# MCU.net
KiCad netlist of a schematic drawn in Altium Designer
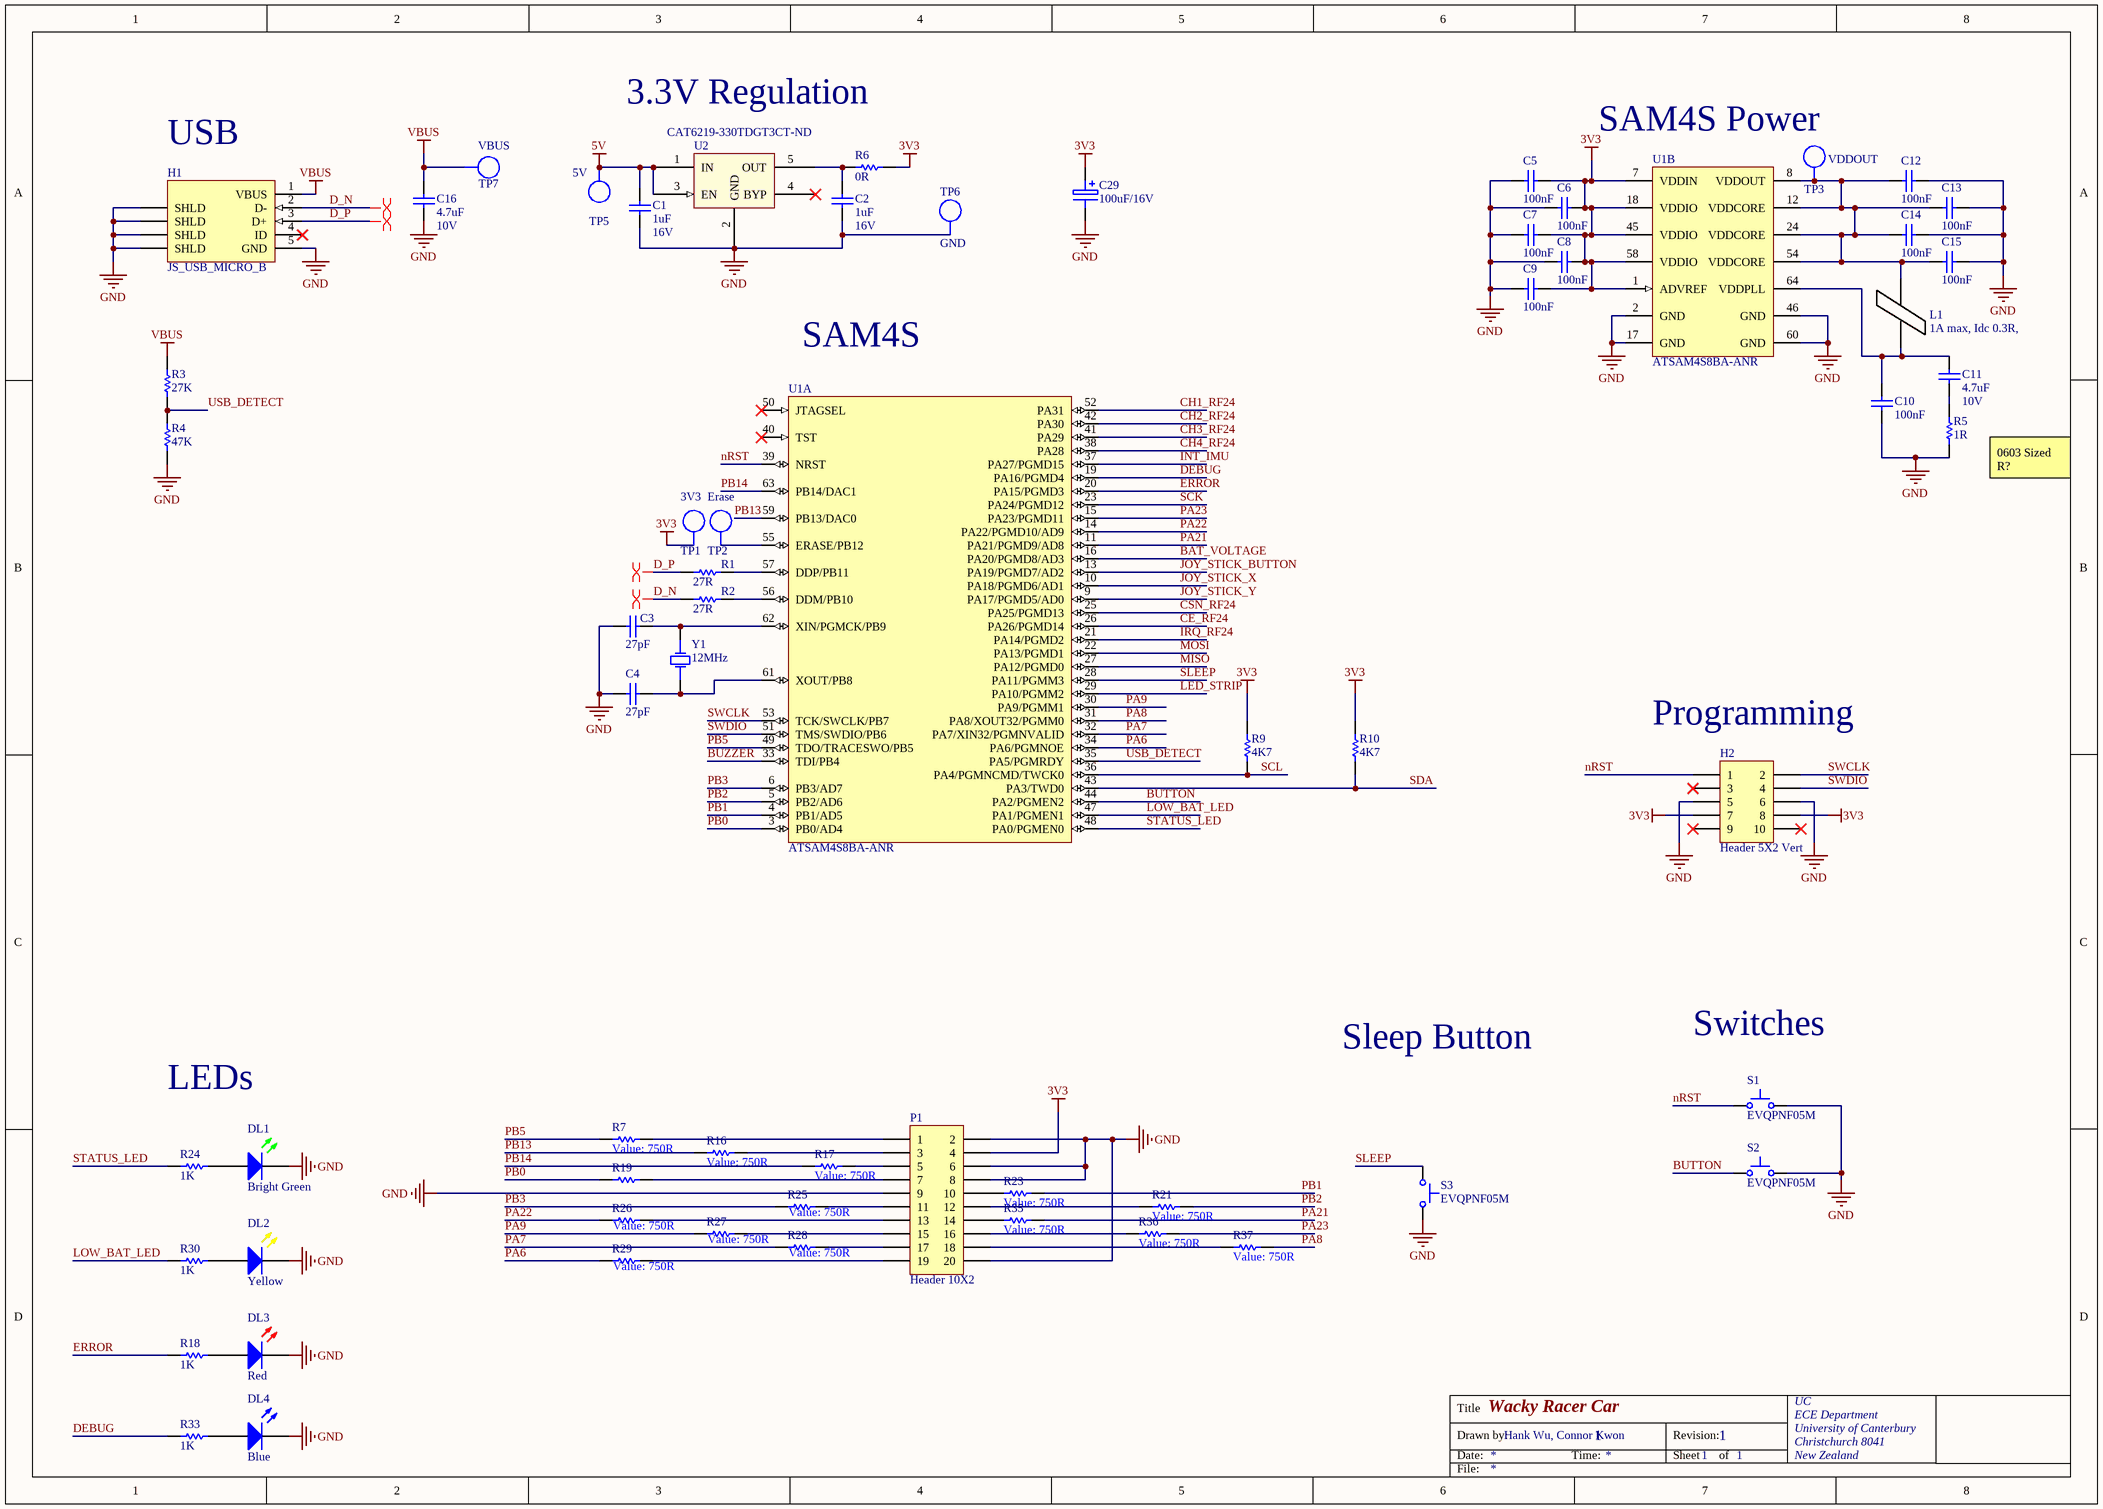
[diagram p0: MCU.SchDoc]

(export (version "E")
  (design (tool "Eeschema 10.0.6"))
  (components
    (comp (ref "C1")
      (value "1uF")
      (footprint "CAPC1608L")
      (description "CAP CER 1uF Y5V -20% +80% 16V 0603")
      (fields (field (name "MAX VOLTAGE") "16V"))
      (libsource (lib "ECE AD19Components_19V1") (part "CC_1uF_0603"))
    )
    (comp (ref "C2")
      (value "1uF")
      (footprint "CAPC1608L")
      (description "CAP CER 1uF Y5V -20% +80% 16V 0603")
      (fields (field (name "MAX VOLTAGE") "16V"))
      (libsource (lib "ECE AD19Components_19V1") (part "CC_1uF_0603"))
    )
    (comp (ref "C3")
      (value "27pF")
      (footprint "CAPC1608L")
      (description "CAP CER 27pF NPO/COG +-5% 50V 0603")
      (libsource (lib "ECE AD19Components_19V1") (part "CC_27pF_0603"))
    )
    (comp (ref "C4")
      (value "27pF")
      (footprint "CAPC1608L")
      (description "CAP CER 27pF NPO/COG +-5% 50V 0603")
      (libsource (lib "ECE AD19Components_19V1") (part "CC_27pF_0603"))
    )
    (comp (ref "C5")
      (value "100nF")
      (footprint "CAPC1608L")
      (description "CAP CER 100nF X7R +-10% 50V 0603")
      (libsource (lib "ECE AD19Components_19V1") (part "CC_100nF_0603"))
    )
    (comp (ref "C6")
      (value "100nF")
      (footprint "CAPC1608L")
      (description "CAP CER 100nF X7R +-10% 50V 0603")
      (libsource (lib "ECE AD19Components_19V1") (part "CC_100nF_0603"))
    )
    (comp (ref "C7")
      (value "100nF")
      (footprint "CAPC1608L")
      (description "CAP CER 100nF X7R +-10% 50V 0603")
      (libsource (lib "ECE AD19Components_19V1") (part "CC_100nF_0603"))
    )
    (comp (ref "C8")
      (value "100nF")
      (footprint "CAPC1608L")
      (description "CAP CER 100nF X7R +-10% 50V 0603")
      (libsource (lib "ECE AD19Components_19V1") (part "CC_100nF_0603"))
    )
    (comp (ref "C9")
      (value "100nF")
      (footprint "CAPC1608L")
      (description "CAP CER 100nF X7R +-10% 50V 0603")
      (libsource (lib "ECE AD19Components_19V1") (part "CC_100nF_0603"))
    )
    (comp (ref "C10")
      (value "100nF")
      (footprint "CAPC1608L")
      (description "CAP CER 100nF X7R +-10% 50V 0603")
      (libsource (lib "ECE AD19Components_19V1") (part "CC_100nF_0603"))
    )
    (comp (ref "C11")
      (value "4.7uF")
      (footprint "CAPC1608N")
      (description "CAP CER 4.7uF X5R +-20%  10V 0603")
      (fields (field (name "MAX VOLTAGE") "10V"))
      (libsource (lib "ECE AD19Components_19V1") (part "CC_4.7uF_0603"))
    )
    (comp (ref "C12")
      (value "100nF")
      (footprint "CAPC1608L")
      (description "CAP CER 100nF X7R +-10% 50V 0603")
      (libsource (lib "ECE AD19Components_19V1") (part "CC_100nF_0603"))
    )
    (comp (ref "C13")
      (value "100nF")
      (footprint "CAPC1608L")
      (description "CAP CER 100nF X7R +-10% 50V 0603")
      (libsource (lib "ECE AD19Components_19V1") (part "CC_100nF_0603"))
    )
    (comp (ref "C14")
      (value "100nF")
      (footprint "CAPC1608L")
      (description "CAP CER 100nF X7R +-10% 50V 0603")
      (libsource (lib "ECE AD19Components_19V1") (part "CC_100nF_0603"))
    )
    (comp (ref "C15")
      (value "100nF")
      (footprint "CAPC1608L")
      (description "CAP CER 100nF X7R +-10% 50V 0603")
      (libsource (lib "ECE AD19Components_19V1") (part "CC_100nF_0603"))
    )
    (comp (ref "C16")
      (value "4.7uF")
      (footprint "CAPC1608N")
      (description "CAP CER 4.7uF X5R +-20%  10V 0603")
      (fields (field (name "MAX VOLTAGE") "10V"))
      (libsource (lib "ECE AD19Components_19V1") (part "CC_4.7uF_0603"))
    )
    (comp (ref "C29")
      (value "100uF/16V")
      (footprint "NICH-1")
      (description "CAP ALUM 100uF 16V SMD")
      (fields (field (name "MANUFACTURER") "Nichcon"))
      (libsource (lib "ECE AD19Components_19V1") (part "CA_100uF_16V"))
    )
    (comp (ref "DL1")
      (value "Bright Green")
      (footprint "WL-SMCW0603")
      (description "LED Bright Green 40mcd 0603 SMD")
      (fields
        (field (name "MANUFACTURER") "WURTH ELEKTRONIK")
        (field (name "MANUFACTURER PART NUMBER") "150060VS75000")
        (field (name "LED COLOUR") "Bright Green")
      )
      (libsource (lib "ECE AD19Components_19V1") (part "DL_150060VS75000"))
    )
    (comp (ref "DL2")
      (value "Yellow")
      (footprint "WL-SMCW0603")
      (description "LED Yellow 120mcd 0603 SMD")
      (fields
        (field (name "MANUFACTURER") "WURTH ELEKTRONIK")
        (field (name "MANUFACTURER PART NUMBER") "150060YS75000")
        (field (name "LED COLOUR") "Yellow")
      )
      (libsource (lib "ECE AD19Components_19V1") (part "DL_150060YS75000"))
    )
    (comp (ref "DL3")
      (value "Red")
      (footprint "WL-SMCW0603")
      (description "LED Red 250mcd 0603 SMD")
      (fields
        (field (name "MANUFACTURER") "WURTH ELEKTRONIK")
        (field (name "MANUFACTURER PART NUMBER") "150060RS75000")
        (field (name "LED COLOUR") "Red")
      )
      (libsource (lib "ECE AD19Components_19V1") (part "DL_150060RS75000"))
    )
    (comp (ref "DL4")
      (value "Blue")
      (footprint "WL-SMCW0603")
      (description "LED Blue 270mcd 0603 SMD")
      (fields
        (field (name "MANUFACTURER") "WURTH ELEKTRONIK")
        (field (name "MANUFACTURER PART NUMBER") "150060BS75000")
        (field (name "LED COLOUR") "Blue")
      )
      (libsource (lib "ECE AD19Components_19V1") (part "DL_150060BS75000"))
    )
    (comp (ref "H1")
      (value "JS_USB_MICRO_B")
      (footprint "FCI_USB_10118194-0001LF")
      (description "CONN USB MICRO B RECPT SMT R/A")
      (fields (field (name "MANUFACTURER") "FCI") (field (name "MANUFACTURER PART NUMBER") "10118194-0001LF"))
      (libsource (lib "ECE AD19Components_19V1") (part "JS_USB_MICRO_B_SMT"))
    )
    (comp (ref "H2")
      (value "Header 5X2 Vert")
      (footprint "IDC2.54-V10D")
      (description "IDC Header, 2,54mm, 10-Pin, Vert")
      (libsource (lib "ECE AD19Components_19V1") (part "JA_HDR_IDC_5X2_VERT"))
    )
    (comp (ref "L1")
      (value "1A max, Idc 0.3R,")
      (footprint "INDC3216L")
      (description "Ferrite Bead, Rdc 0.3R, Z100MHZ 600R, Imax 1A, SMD 1206")
      (fields
        (field (name "MANUFACTURER") "FAIR-RITE")
        (field (name "MANUFACTURER PART NUMBER") "2512066017Y1")
      )
      (libsource (lib "ECE AD19Components_19V1") (part "IN_Ferrite-Bead"))
    )
    (comp (ref "P1")
      (value "Header 10X2")
      (footprint "HDR2X10")
      (description "Header, 10-Pin, Dual row")
      (fields (field (name "PUBLISHER") "Altium Limited"))
      (libsource (lib "Miscellaneous Connectors") (part "Header 10X2"))
    )
    (comp (ref "R1")
      (value "27R")
      (footprint "RESC1608L")
      (description "RES 27 OHM 1/10W 5% 0603 SMD")
      (libsource (lib "ECE AD19Components_19V1") (part "RS_27R"))
    )
    (comp (ref "R2")
      (value "27R")
      (footprint "RESC1608L")
      (description "RES 27 OHM 1/10W 5% 0603 SMD")
      (libsource (lib "ECE AD19Components_19V1") (part "RS_27R"))
    )
    (comp (ref "R3")
      (value "27K")
      (footprint "RESC1608L")
      (description "RES 27K OHM 1/10W 5% 0603 SMD")
      (libsource (lib "ECE AD19Components_19V1") (part "RS_27K"))
    )
    (comp (ref "R4")
      (value "47K")
      (footprint "RESC1608L")
      (description "RES 27K OHM 1/10W 5% 0603 SMD")
      (libsource (lib "ECE AD19Components_19V1") (part "RS_27K"))
    )
    (comp (ref "R5")
      (value "1R")
      (footprint "RESC3216L")
      (description "RES 1R OHM 1/4W 5% 1206 SMD")
      (libsource (lib "ECE AD19Components_19V1") (part "RT_1R"))
    )
    (comp (ref "R6")
      (value "0R")
      (footprint "RESC1608L")
      (description "RES 0.0 OHM 1/10W 5% 0603 SMD")
      (libsource (lib "ECE AD19Components_19V1") (part "RS_0R0"))
    )
    (comp (ref "R7")
      (value "750R")
      (footprint "RESC1608L")
      (description "RES 750 OHM 1/10W 5% 0603 SMD")
      (libsource (lib "ECE AD19Components_19V1") (part "RS_750R"))
    )
    (comp (ref "R9")
      (value "4K7")
      (footprint "RESC1608L")
      (description "RES 4.7K OHM 1/10W 5% 0603 SMD")
      (libsource (lib "ECE AD19Components_19V1") (part "RS_4K7"))
    )
    (comp (ref "R10")
      (value "4K7")
      (footprint "RESC1608L")
      (description "RES 4.7K OHM 1/10W 5% 0603 SMD")
      (libsource (lib "ECE AD19Components_19V1") (part "RS_4K7"))
    )
    (comp (ref "R16")
      (value "750R")
      (footprint "RESC1608L")
      (description "RES 750 OHM 1/10W 5% 0603 SMD")
      (libsource (lib "ECE AD19Components_19V1") (part "RS_750R"))
    )
    (comp (ref "R17")
      (value "750R")
      (footprint "RESC1608L")
      (description "RES 750 OHM 1/10W 5% 0603 SMD")
      (libsource (lib "ECE AD19Components_19V1") (part "RS_750R"))
    )
    (comp (ref "R18")
      (value "1K")
      (footprint "RESC1608L")
      (description "RES 1.0K OHM 1/10W 5% 0603 SMD")
      (libsource (lib "ECE AD19Components_19V1") (part "RS_1K"))
    )
    (comp (ref "R19")
      (value "~")
      (footprint "RESC1608L")
      (description "RES 750 OHM 1/10W 5% 0603 SMD")
      (libsource (lib "ECE AD19Components_19V1") (part "RS_750R"))
    )
    (comp (ref "R21")
      (value "750R")
      (footprint "RESC1608L")
      (description "RES 750 OHM 1/10W 5% 0603 SMD")
      (libsource (lib "ECE AD19Components_19V1") (part "RS_750R"))
    )
    (comp (ref "R23")
      (value "750R")
      (footprint "RESC1608L")
      (description "RES 750 OHM 1/10W 5% 0603 SMD")
      (libsource (lib "ECE AD19Components_19V1") (part "RS_750R"))
    )
    (comp (ref "R24")
      (value "1K")
      (footprint "RESC1608L")
      (description "RES 1.0K OHM 1/10W 5% 0603 SMD")
      (libsource (lib "ECE AD19Components_19V1") (part "RS_1K"))
    )
    (comp (ref "R25")
      (value "750R")
      (footprint "RESC1608L")
      (description "RES 750 OHM 1/10W 5% 0603 SMD")
      (libsource (lib "ECE AD19Components_19V1") (part "RS_750R"))
    )
    (comp (ref "R26")
      (value "750R")
      (footprint "RESC1608L")
      (description "RES 750 OHM 1/10W 5% 0603 SMD")
      (libsource (lib "ECE AD19Components_19V1") (part "RS_750R"))
    )
    (comp (ref "R27")
      (value "750R")
      (footprint "RESC1608L")
      (description "RES 750 OHM 1/10W 5% 0603 SMD")
      (libsource (lib "ECE AD19Components_19V1") (part "RS_750R"))
    )
    (comp (ref "R28")
      (value "750R")
      (footprint "RESC1608L")
      (description "RES 750 OHM 1/10W 5% 0603 SMD")
      (libsource (lib "ECE AD19Components_19V1") (part "RS_750R"))
    )
    (comp (ref "R29")
      (value "750R")
      (footprint "RESC1608L")
      (description "RES 750 OHM 1/10W 5% 0603 SMD")
      (libsource (lib "ECE AD19Components_19V1") (part "RS_750R"))
    )
    (comp (ref "R30")
      (value "1K")
      (footprint "RESC1608L")
      (description "RES 1.0K OHM 1/10W 5% 0603 SMD")
      (libsource (lib "ECE AD19Components_19V1") (part "RS_1K"))
    )
    (comp (ref "R33")
      (value "1K")
      (footprint "RESC1608L")
      (description "RES 1.0K OHM 1/10W 5% 0603 SMD")
      (libsource (lib "ECE AD19Components_19V1") (part "RS_1K"))
    )
    (comp (ref "R35")
      (value "750R")
      (footprint "RESC1608L")
      (description "RES 750 OHM 1/10W 5% 0603 SMD")
      (libsource (lib "ECE AD19Components_19V1") (part "RS_750R"))
    )
    (comp (ref "R36")
      (value "750R")
      (footprint "RESC1608L")
      (description "RES 750 OHM 1/10W 5% 0603 SMD")
      (libsource (lib "ECE AD19Components_19V1") (part "RS_750R"))
    )
    (comp (ref "R37")
      (value "750R")
      (footprint "RESC1608L")
      (description "RES 750 OHM 1/10W 5% 0603 SMD")
      (libsource (lib "ECE AD19Components_19V1") (part "RS_750R"))
    )
    (comp (ref "S1")
      (value "EVQPNF05M")
      (footprint "EVQPNF05M")
      (description "Panasonic 6 x 3.5mm SMD Light Touch Switch Type SMD")
      (fields (field (name "MANUFACTURER") "Panasonic"))
      (libsource (lib "ECE AD19Components_19V1") (part "WS_EVQPNF05M"))
    )
    (comp (ref "S2")
      (value "EVQPNF05M")
      (footprint "EVQPNF05M")
      (description "Panasonic 6 x 3.5mm SMD Light Touch Switch Type SMD")
      (fields (field (name "MANUFACTURER") "Panasonic"))
      (libsource (lib "ECE AD19Components_19V1") (part "WS_EVQPNF05M"))
    )
    (comp (ref "S3")
      (value "EVQPNF05M")
      (footprint "EVQPNF05M")
      (description "Panasonic 6 x 3.5mm SMD Light Touch Switch Type SMD")
      (fields (field (name "MANUFACTURER") "Panasonic"))
      (libsource (lib "ECE AD19Components_19V1") (part "WS_EVQPNF05M"))
    )
    (comp (ref "TP1")
      (value "3V3")
      (footprint "TP_1206")
      (description "Test-Point 3.3x1.6x2.1mm SMD")
      (fields
        (field (name "MANUFACTURER") "Harwin Inc")
        (field (name "MANUFACTURER PART NUMBER") "S1751-46R")
      )
      (libsource (lib "ECE AD19Components_19V1") (part "TP_1206"))
    )
    (comp (ref "TP2")
      (value "Erase")
      (footprint "TP_1206")
      (description "Test-Point 3.3x1.6x2.1mm SMD")
      (fields
        (field (name "MANUFACTURER") "Harwin Inc")
        (field (name "MANUFACTURER PART NUMBER") "S1751-46R")
      )
      (libsource (lib "ECE AD19Components_19V1") (part "TP_1206"))
    )
    (comp (ref "TP3")
      (value "VDDOUT")
      (footprint "TP_1206")
      (description "Test-Point 3.3x1.6x2.1mm SMD")
      (fields
        (field (name "MANUFACTURER") "Harwin Inc")
        (field (name "MANUFACTURER PART NUMBER") "S1751-46R")
      )
      (libsource (lib "ECE AD19Components_19V1") (part "TP_1206"))
    )
    (comp (ref "TP5")
      (value "5V")
      (footprint "TP_1206")
      (description "Test-Point 3.3x1.6x2.1mm SMD")
      (fields
        (field (name "MANUFACTURER") "Harwin Inc")
        (field (name "MANUFACTURER PART NUMBER") "S1751-46R")
      )
      (libsource (lib "ECE AD19Components_19V1") (part "TP_1206"))
    )
    (comp (ref "TP6")
      (value "GND")
      (footprint "TP_1206")
      (description "Test-Point 3.3x1.6x2.1mm SMD")
      (fields
        (field (name "MANUFACTURER") "Harwin Inc")
        (field (name "MANUFACTURER PART NUMBER") "S1751-46R")
      )
      (libsource (lib "ECE AD19Components_19V1") (part "TP_1206"))
    )
    (comp (ref "TP7")
      (value "VBUS")
      (footprint "TP_1206")
      (description "Test-Point 3.3x1.6x2.1mm SMD")
      (fields
        (field (name "MANUFACTURER") "Harwin Inc")
        (field (name "MANUFACTURER PART NUMBER") "S1751-46R")
      )
      (libsource (lib "ECE AD19Components_19V1") (part "TP_1206"))
    )
    (comp (ref "U1")
      (value "ATSAM4S8BA-ANR")
      (footprint "LQFP64_L")
      (description "IC MCU 32BIT 512KB FLASH 64LQFP")
      (fields (field (name "MANUFACTURER") "Atmel"))
      (libsource (lib "") (part "SE_ATSAM4S16BA-MU_1"))
    )
    (comp (ref "U2")
      (value "CAT6219-330TDGT3")
      (footprint "SOT95P280X145-5N")
      (description "IC REG LIN 3.3V 500MA TSOT23-5")
      (fields
        (field (name "BASE PART NUMBER") "CAT6219")
        (field (name "SUPPLIER PART NUMBER") "CAT6219-330TDGT3CT-ND")
      )
      (libsource (lib "ENCE461AD19_19V2") (part "SV_CAT6219-330TDGT3"))
    )
    (comp (ref "Y1")
      (value "12MHz")
      (footprint "6.0X3.5-4")
      (description "CRYSTAL 12MHZ 18PF 6X3.5mm SMD")
      (fields
        (field (name "MANUFACTURER") "CTS-Frequency Controls")
        (field (name "MANUFACTURER PART NUMBER") "406C35D12M00000")
        (field (name "FREQUENCY") "12MHz")
      )
      (libsource (lib "ECE AD19Components_19V1") (part "XT_CRYSTAL_12MHz_18pF"))
    )
  )
  (nets
    (net (code "1") (name "/BAT_VOLTAGE") (class "Default")
      (node (ref "U1") (pin "16") (pinfunction "PA20/PGMD8/AD3_16") (pintype "bidirectional"))
    )
    (net (code "2") (name "/BUTTON") (class "Default")
      (node (ref "S2") (pin "1") (pintype "passive"))
      (node (ref "U1") (pin "44") (pinfunction "PA2/PGMEN2_44") (pintype "bidirectional"))
    )
    (net (code "3") (name "/BUZZER") (class "Default")
      (node (ref "U1") (pin "33") (pinfunction "TDI/PB4_33") (pintype "bidirectional"))
    )
    (net (code "4") (name "/CE_RF24") (class "Default")
      (node (ref "U1") (pin "26") (pinfunction "PA26/PGMD14_26") (pintype "bidirectional"))
    )
    (net (code "5") (name "/CH1_RF24") (class "Default")
      (node (ref "U1") (pin "52") (pinfunction "PA31_52") (pintype "bidirectional"))
    )
    (net (code "6") (name "/CH2_RF24") (class "Default")
      (node (ref "U1") (pin "42") (pinfunction "PA30_42") (pintype "bidirectional"))
    )
    (net (code "7") (name "/CH3_RF24") (class "Default")
      (node (ref "U1") (pin "41") (pinfunction "PA29_41") (pintype "bidirectional"))
    )
    (net (code "8") (name "/CH4_RF24") (class "Default")
      (node (ref "U1") (pin "38") (pinfunction "PA28_38") (pintype "bidirectional"))
    )
    (net (code "9") (name "/CSN_RF24") (class "Default")
      (node (ref "U1") (pin "25") (pinfunction "PA25/PGMD13_25") (pintype "bidirectional"))
    )
    (net (code "10") (name "/DEBUG") (class "Default")
      (node (ref "R33") (pin "1") (pinfunction "1_1") (pintype "passive"))
      (node (ref "U1") (pin "19") (pinfunction "PA16/PGMD4_19") (pintype "bidirectional"))
    )
    (net (code "11") (name "/D_N") (class "Default")
      (node (ref "H1") (pin "2") (pinfunction "D-_2") (pintype "input"))
      (node (ref "R2") (pin "1") (pinfunction "1_1") (pintype "passive"))
    )
    (net (code "12") (name "/D_P") (class "Default")
      (node (ref "H1") (pin "3") (pinfunction "D+_3") (pintype "input"))
      (node (ref "R1") (pin "1") (pinfunction "1_1") (pintype "passive"))
    )
    (net (code "13") (name "/ERROR") (class "Default")
      (node (ref "R18") (pin "1") (pinfunction "1_1") (pintype "passive"))
      (node (ref "U1") (pin "20") (pinfunction "PA15/PGMD3_20") (pintype "bidirectional"))
    )
    (net (code "14") (name "/INT_IMU") (class "Default")
      (node (ref "U1") (pin "37") (pinfunction "PA27/PGMD15_37") (pintype "bidirectional"))
    )
    (net (code "15") (name "/IRQ_RF24") (class "Default")
      (node (ref "U1") (pin "21") (pinfunction "PA14/PGMD2_21") (pintype "bidirectional"))
    )
    (net (code "16") (name "/JOY_STICK_BUTTON") (class "Default")
      (node (ref "U1") (pin "13") (pinfunction "PA19/PGMD7/AD2_13") (pintype "bidirectional"))
    )
    (net (code "17") (name "/JOY_STICK_X") (class "Default")
      (node (ref "U1") (pin "10") (pinfunction "PA18/PGMD6/AD1_10") (pintype "bidirectional"))
    )
    (net (code "18") (name "/JOY_STICK_Y") (class "Default")
      (node (ref "U1") (pin "9") (pinfunction "PA17/PGMD5/AD0_9") (pintype "bidirectional"))
    )
    (net (code "19") (name "/LED_STRIP") (class "Default")
      (node (ref "U1") (pin "29") (pinfunction "PA10/PGMM2_29") (pintype "bidirectional"))
    )
    (net (code "20") (name "/LOW_BAT_LED") (class "Default")
      (node (ref "R30") (pin "1") (pinfunction "1_1") (pintype "passive"))
      (node (ref "U1") (pin "47") (pinfunction "PA1/PGMEN1_47") (pintype "bidirectional"))
    )
    (net (code "21") (name "/MISO") (class "Default")
      (node (ref "U1") (pin "27") (pinfunction "PA12/PGMD0_27") (pintype "bidirectional"))
    )
    (net (code "22") (name "/MOSI") (class "Default")
      (node (ref "U1") (pin "22") (pinfunction "PA13/PGMD1_22") (pintype "bidirectional"))
    )
    (net (code "23") (name "/PA6") (class "Default")
      (node (ref "R29") (pin "1") (pinfunction "1_1") (pintype "passive"))
      (node (ref "U1") (pin "34") (pinfunction "PA6/PGMNOE_34") (pintype "bidirectional"))
    )
    (net (code "24") (name "/PA7") (class "Default")
      (node (ref "R28") (pin "1") (pinfunction "1_1") (pintype "passive"))
      (node (ref "U1") (pin "32") (pinfunction "PA7/XIN32/PGMNVALID_32") (pintype "bidirectional"))
    )
    (net (code "25") (name "/PA8") (class "Default")
      (node (ref "R37") (pin "2") (pinfunction "2_2") (pintype "passive"))
      (node (ref "U1") (pin "31") (pinfunction "PA8/XOUT32/PGMM0_31") (pintype "bidirectional"))
    )
    (net (code "26") (name "/PA9") (class "Default")
      (node (ref "R27") (pin "1") (pinfunction "1_1") (pintype "passive"))
      (node (ref "U1") (pin "30") (pinfunction "PA9/PGMM1_30") (pintype "bidirectional"))
    )
    (net (code "27") (name "/PA21") (class "Default")
      (node (ref "R35") (pin "2") (pinfunction "2_2") (pintype "passive"))
      (node (ref "U1") (pin "11") (pinfunction "PA21/PGMD9/AD8_11") (pintype "bidirectional"))
    )
    (net (code "28") (name "/PA22") (class "Default")
      (node (ref "R26") (pin "1") (pinfunction "1_1") (pintype "passive"))
      (node (ref "U1") (pin "14") (pinfunction "PA22/PGMD10/AD9_14") (pintype "bidirectional"))
    )
    (net (code "29") (name "/PA23") (class "Default")
      (node (ref "R36") (pin "2") (pinfunction "2_2") (pintype "passive"))
      (node (ref "U1") (pin "15") (pinfunction "PA23/PGMD11_15") (pintype "bidirectional"))
    )
    (net (code "30") (name "/PB0") (class "Default")
      (node (ref "R19") (pin "1") (pinfunction "1_1") (pintype "passive"))
      (node (ref "U1") (pin "3") (pinfunction "PB0/AD4_3") (pintype "bidirectional"))
    )
    (net (code "31") (name "/PB1") (class "Default")
      (node (ref "R23") (pin "2") (pinfunction "2_2") (pintype "passive"))
      (node (ref "U1") (pin "4") (pinfunction "PB1/AD5_4") (pintype "bidirectional"))
    )
    (net (code "32") (name "/PB2") (class "Default")
      (node (ref "R21") (pin "2") (pinfunction "2_2") (pintype "passive"))
      (node (ref "U1") (pin "5") (pinfunction "PB2/AD6_5") (pintype "bidirectional"))
    )
    (net (code "33") (name "/PB3") (class "Default")
      (node (ref "R25") (pin "1") (pinfunction "1_1") (pintype "passive"))
      (node (ref "U1") (pin "6") (pinfunction "PB3/AD7_6") (pintype "bidirectional"))
    )
    (net (code "34") (name "/PB5") (class "Default")
      (node (ref "R7") (pin "1") (pinfunction "1_1") (pintype "passive"))
      (node (ref "U1") (pin "49") (pinfunction "TDO/TRACESWO/PB5_49") (pintype "bidirectional"))
    )
    (net (code "35") (name "/PB13") (class "Default")
      (node (ref "R16") (pin "1") (pinfunction "1_1") (pintype "passive"))
      (node (ref "U1") (pin "59") (pinfunction "PB13/DAC0_59") (pintype "bidirectional"))
    )
    (net (code "36") (name "/PB14") (class "Default")
      (node (ref "R17") (pin "1") (pinfunction "1_1") (pintype "passive"))
      (node (ref "U1") (pin "63") (pinfunction "PB14/DAC1_63") (pintype "bidirectional"))
    )
    (net (code "37") (name "/SCK") (class "Default")
      (node (ref "U1") (pin "23") (pinfunction "PA24/PGMD12_23") (pintype "bidirectional"))
    )
    (net (code "38") (name "/SCL") (class "Default")
      (node (ref "R9") (pin "1") (pinfunction "1_1") (pintype "passive"))
      (node (ref "U1") (pin "36") (pinfunction "PA4/PGMNCMD/TWCK0_36") (pintype "bidirectional"))
    )
    (net (code "39") (name "/SDA") (class "Default")
      (node (ref "R10") (pin "1") (pinfunction "1_1") (pintype "passive"))
      (node (ref "U1") (pin "43") (pinfunction "PA3/TWD0_43") (pintype "bidirectional"))
    )
    (net (code "40") (name "/SLEEP") (class "Default")
      (node (ref "S3") (pin "1") (pintype "passive"))
      (node (ref "U1") (pin "28") (pinfunction "PA11/PGMM3_28") (pintype "bidirectional"))
    )
    (net (code "41") (name "/STATUS_LED") (class "Default")
      (node (ref "R24") (pin "1") (pinfunction "1_1") (pintype "passive"))
      (node (ref "U1") (pin "48") (pinfunction "PA0/PGMEN0_48") (pintype "bidirectional"))
    )
    (net (code "42") (name "/SWCLK") (class "Default")
      (node (ref "H2") (pin "2") (pinfunction "2_2") (pintype "passive"))
      (node (ref "U1") (pin "53") (pinfunction "TCK/SWCLK/PB7_53") (pintype "bidirectional"))
    )
    (net (code "43") (name "/SWDIO") (class "Default")
      (node (ref "H2") (pin "4") (pinfunction "4_4") (pintype "passive"))
      (node (ref "U1") (pin "51") (pinfunction "TMS/SWDIO/PB6_51") (pintype "bidirectional"))
    )
    (net (code "44") (name "/USB_DETECT") (class "Default")
      (node (ref "R3") (pin "1") (pinfunction "1_1") (pintype "passive"))
      (node (ref "R4") (pin "2") (pinfunction "2_2") (pintype "passive"))
      (node (ref "U1") (pin "35") (pinfunction "PA5/PGMRDY_35") (pintype "bidirectional"))
    )
    (net (code "45") (name "/nRST") (class "Default")
      (node (ref "H2") (pin "1") (pinfunction "1_1") (pintype "passive"))
      (node (ref "S1") (pin "1") (pintype "passive"))
      (node (ref "U1") (pin "39") (pinfunction "NRST_39") (pintype "bidirectional"))
    )
    (net (code "46") (name "3V3") (class "Default")
      (node (ref "C29") (pin "2") (pintype "passive"))
      (node (ref "C5") (pin "2") (pinfunction "2_2") (pintype "passive"))
      (node (ref "C6") (pin "2") (pinfunction "2_2") (pintype "passive"))
      (node (ref "C7") (pin "2") (pinfunction "2_2") (pintype "passive"))
      (node (ref "C8") (pin "2") (pinfunction "2_2") (pintype "passive"))
      (node (ref "C9") (pin "2") (pinfunction "2_2") (pintype "passive"))
      (node (ref "H2") (pin "7") (pinfunction "7_7") (pintype "passive"))
      (node (ref "H2") (pin "8") (pinfunction "8_8") (pintype "passive"))
      (node (ref "P1") (pin "4") (pinfunction "4_4") (pintype "passive"))
      (node (ref "R10") (pin "2") (pinfunction "2_2") (pintype "passive"))
      (node (ref "R6") (pin "2") (pinfunction "2_2") (pintype "passive"))
      (node (ref "R9") (pin "2") (pinfunction "2_2") (pintype "passive"))
      (node (ref "TP1") (pin "1") (pinfunction "1_1") (pintype "passive"))
      (node (ref "U1") (pin "1") (pinfunction "ADVREF_1") (pintype "input"))
      (node (ref "U1") (pin "18") (pinfunction "VDDIO_18") (pintype "power_in"))
      (node (ref "U1") (pin "45") (pinfunction "VDDIO_45") (pintype "power_in"))
      (node (ref "U1") (pin "58") (pinfunction "VDDIO_58") (pintype "power_in"))
      (node (ref "U1") (pin "7") (pinfunction "VDDIN_7") (pintype "power_in"))
    )
    (net (code "47") (name "5V") (class "Default")
      (node (ref "C1") (pin "2") (pinfunction "2_2") (pintype "passive"))
      (node (ref "TP5") (pin "1") (pinfunction "1_1") (pintype "passive"))
      (node (ref "U2") (pin "1") (pinfunction "IN_1") (pintype "power_in"))
      (node (ref "U2") (pin "3") (pinfunction "EN_3") (pintype "input"))
    )
    (net (code "48") (name "GND") (class "Default")
      (node (ref "C1") (pin "1") (pinfunction "1_1") (pintype "passive"))
      (node (ref "C10") (pin "1") (pinfunction "1_1") (pintype "passive"))
      (node (ref "C12") (pin "2") (pinfunction "2_2") (pintype "passive"))
      (node (ref "C13") (pin "2") (pinfunction "2_2") (pintype "passive"))
      (node (ref "C14") (pin "2") (pinfunction "2_2") (pintype "passive"))
      (node (ref "C15") (pin "2") (pinfunction "2_2") (pintype "passive"))
      (node (ref "C16") (pin "1") (pinfunction "1_1") (pintype "passive"))
      (node (ref "C2") (pin "1") (pinfunction "1_1") (pintype "passive"))
      (node (ref "C29") (pin "1") (pintype "passive"))
      (node (ref "C3") (pin "1") (pinfunction "1_1") (pintype "passive"))
      (node (ref "C4") (pin "1") (pinfunction "1_1") (pintype "passive"))
      (node (ref "C5") (pin "1") (pinfunction "1_1") (pintype "passive"))
      (node (ref "C6") (pin "1") (pinfunction "1_1") (pintype "passive"))
      (node (ref "C7") (pin "1") (pinfunction "1_1") (pintype "passive"))
      (node (ref "C8") (pin "1") (pinfunction "1_1") (pintype "passive"))
      (node (ref "C9") (pin "1") (pinfunction "1_1") (pintype "passive"))
      (node (ref "DL1") (pin "1") (pinfunction "K_1") (pintype "passive"))
      (node (ref "DL2") (pin "1") (pinfunction "K_1") (pintype "passive"))
      (node (ref "DL3") (pin "1") (pinfunction "K_1") (pintype "passive"))
      (node (ref "DL4") (pin "1") (pinfunction "K_1") (pintype "passive"))
      (node (ref "H1") (pin "5") (pinfunction "GND_5") (pintype "passive"))
      (node (ref "H1") (pin "6") (pinfunction "SHLD_6") (pintype "passive"))
      (node (ref "H2") (pin "5") (pinfunction "5_5") (pintype "passive"))
      (node (ref "H2") (pin "6") (pinfunction "6_6") (pintype "passive"))
      (node (ref "P1") (pin "2") (pinfunction "2_2") (pintype "passive"))
      (node (ref "P1") (pin "20") (pinfunction "20_20") (pintype "passive"))
      (node (ref "P1") (pin "6") (pinfunction "6_6") (pintype "passive"))
      (node (ref "P1") (pin "8") (pinfunction "8_8") (pintype "passive"))
      (node (ref "P1") (pin "9") (pinfunction "9_9") (pintype "passive"))
      (node (ref "R4") (pin "1") (pinfunction "1_1") (pintype "passive"))
      (node (ref "R5") (pin "1") (pinfunction "1_1") (pintype "passive"))
      (node (ref "S1") (pin "2") (pintype "passive"))
      (node (ref "S2") (pin "2") (pintype "passive"))
      (node (ref "S3") (pin "2") (pintype "passive"))
      (node (ref "TP6") (pin "1") (pinfunction "1_1") (pintype "passive"))
      (node (ref "U1") (pin "17") (pinfunction "GND_17") (pintype "power_in"))
      (node (ref "U1") (pin "2") (pinfunction "GND_2") (pintype "power_in"))
      (node (ref "U1") (pin "46") (pinfunction "GND_46") (pintype "power_in"))
      (node (ref "U1") (pin "60") (pinfunction "GND_60") (pintype "power_in"))
      (node (ref "U2") (pin "2") (pinfunction "GND_2") (pintype "power_in"))
    )
    (net (code "49") (name "Net-(C11-Pad1)") (class "Default")
      (node (ref "C11") (pin "1") (pinfunction "1_1") (pintype "passive"))
      (node (ref "R5") (pin "2") (pinfunction "2_2") (pintype "passive"))
    )
    (net (code "50") (name "Net-(DL1-A)") (class "Default")
      (node (ref "DL1") (pin "2") (pinfunction "A_2") (pintype "passive"))
      (node (ref "R24") (pin "2") (pinfunction "2_2") (pintype "passive"))
    )
    (net (code "51") (name "Net-(DL2-A)") (class "Default")
      (node (ref "DL2") (pin "2") (pinfunction "A_2") (pintype "passive"))
      (node (ref "R30") (pin "2") (pinfunction "2_2") (pintype "passive"))
    )
    (net (code "52") (name "Net-(DL3-A)") (class "Default")
      (node (ref "DL3") (pin "2") (pinfunction "A_2") (pintype "passive"))
      (node (ref "R18") (pin "2") (pinfunction "2_2") (pintype "passive"))
    )
    (net (code "53") (name "Net-(DL4-A)") (class "Default")
      (node (ref "DL4") (pin "2") (pinfunction "A_2") (pintype "passive"))
      (node (ref "R33") (pin "2") (pinfunction "2_2") (pintype "passive"))
    )
    (net (code "54") (name "Net-(P1-Pad1)") (class "Default")
      (node (ref "P1") (pin "1") (pinfunction "1_1") (pintype "passive"))
      (node (ref "R7") (pin "2") (pinfunction "2_2") (pintype "passive"))
    )
    (net (code "55") (name "Net-(P1-Pad3)") (class "Default")
      (node (ref "P1") (pin "3") (pinfunction "3_3") (pintype "passive"))
      (node (ref "R16") (pin "2") (pinfunction "2_2") (pintype "passive"))
    )
    (net (code "56") (name "Net-(P1-Pad5)") (class "Default")
      (node (ref "P1") (pin "5") (pinfunction "5_5") (pintype "passive"))
      (node (ref "R17") (pin "2") (pinfunction "2_2") (pintype "passive"))
    )
    (net (code "57") (name "Net-(P1-Pad7)") (class "Default")
      (node (ref "P1") (pin "7") (pinfunction "7_7") (pintype "passive"))
      (node (ref "R19") (pin "2") (pinfunction "2_2") (pintype "passive"))
    )
    (net (code "58") (name "Net-(P1-Pad10)") (class "Default")
      (node (ref "P1") (pin "10") (pinfunction "10_10") (pintype "passive"))
      (node (ref "R23") (pin "1") (pinfunction "1_1") (pintype "passive"))
    )
    (net (code "59") (name "Net-(P1-Pad11)") (class "Default")
      (node (ref "P1") (pin "11") (pinfunction "11_11") (pintype "passive"))
      (node (ref "R25") (pin "2") (pinfunction "2_2") (pintype "passive"))
    )
    (net (code "60") (name "Net-(P1-Pad12)") (class "Default")
      (node (ref "P1") (pin "12") (pinfunction "12_12") (pintype "passive"))
      (node (ref "R21") (pin "1") (pinfunction "1_1") (pintype "passive"))
    )
    (net (code "61") (name "Net-(P1-Pad13)") (class "Default")
      (node (ref "P1") (pin "13") (pinfunction "13_13") (pintype "passive"))
      (node (ref "R26") (pin "2") (pinfunction "2_2") (pintype "passive"))
    )
    (net (code "62") (name "Net-(P1-Pad14)") (class "Default")
      (node (ref "P1") (pin "14") (pinfunction "14_14") (pintype "passive"))
      (node (ref "R35") (pin "1") (pinfunction "1_1") (pintype "passive"))
    )
    (net (code "63") (name "Net-(P1-Pad15)") (class "Default")
      (node (ref "P1") (pin "15") (pinfunction "15_15") (pintype "passive"))
      (node (ref "R27") (pin "2") (pinfunction "2_2") (pintype "passive"))
    )
    (net (code "64") (name "Net-(P1-Pad16)") (class "Default")
      (node (ref "P1") (pin "16") (pinfunction "16_16") (pintype "passive"))
      (node (ref "R36") (pin "1") (pinfunction "1_1") (pintype "passive"))
    )
    (net (code "65") (name "Net-(P1-Pad17)") (class "Default")
      (node (ref "P1") (pin "17") (pinfunction "17_17") (pintype "passive"))
      (node (ref "R28") (pin "2") (pinfunction "2_2") (pintype "passive"))
    )
    (net (code "66") (name "Net-(P1-Pad18)") (class "Default")
      (node (ref "P1") (pin "18") (pinfunction "18_18") (pintype "passive"))
      (node (ref "R37") (pin "1") (pinfunction "1_1") (pintype "passive"))
    )
    (net (code "67") (name "Net-(P1-Pad19)") (class "Default")
      (node (ref "P1") (pin "19") (pinfunction "19_19") (pintype "passive"))
      (node (ref "R29") (pin "2") (pinfunction "2_2") (pintype "passive"))
    )
    (net (code "68") (name "Net-(U1A-DDM{slash}PB10)") (class "Default")
      (node (ref "R2") (pin "2") (pinfunction "2_2") (pintype "passive"))
      (node (ref "U1") (pin "56") (pinfunction "DDM/PB10_56") (pintype "bidirectional"))
    )
    (net (code "69") (name "Net-(U1A-DDP{slash}PB11)") (class "Default")
      (node (ref "R1") (pin "2") (pinfunction "2_2") (pintype "passive"))
      (node (ref "U1") (pin "57") (pinfunction "DDP/PB11_57") (pintype "bidirectional"))
    )
    (net (code "70") (name "Net-(U1A-ERASE{slash}PB12)") (class "Default")
      (node (ref "TP2") (pin "1") (pinfunction "1_1") (pintype "passive"))
      (node (ref "U1") (pin "55") (pinfunction "ERASE/PB12_55") (pintype "bidirectional"))
    )
    (net (code "71") (name "Net-(U1A-XIN{slash}PGMCK{slash}PB9)") (class "Default")
      (node (ref "C3") (pin "2") (pinfunction "2_2") (pintype "passive"))
      (node (ref "U1") (pin "62") (pinfunction "XIN/PGMCK/PB9_62") (pintype "bidirectional"))
      (node (ref "Y1") (pin "3") (pinfunction "OSC2_3") (pintype "passive"))
    )
    (net (code "72") (name "Net-(U1A-XOUT{slash}PB8)") (class "Default")
      (node (ref "C4") (pin "2") (pinfunction "2_2") (pintype "passive"))
      (node (ref "U1") (pin "61") (pinfunction "XOUT/PB8_61") (pintype "bidirectional"))
      (node (ref "Y1") (pin "1") (pinfunction "OSC1_1") (pintype "passive"))
    )
    (net (code "73") (name "Net-(U1B-VDDOUT)") (class "Default")
      (node (ref "C12") (pin "1") (pinfunction "1_1") (pintype "passive"))
      (node (ref "C13") (pin "1") (pinfunction "1_1") (pintype "passive"))
      (node (ref "C14") (pin "1") (pinfunction "1_1") (pintype "passive"))
      (node (ref "C15") (pin "1") (pinfunction "1_1") (pintype "passive"))
      (node (ref "L1") (pin "2") (pinfunction "2_2") (pintype "passive"))
      (node (ref "TP3") (pin "1") (pinfunction "1_1") (pintype "passive"))
      (node (ref "U1") (pin "12") (pinfunction "VDDCORE_12") (pintype "power_in"))
      (node (ref "U1") (pin "24") (pinfunction "VDDCORE_24") (pintype "power_in"))
      (node (ref "U1") (pin "54") (pinfunction "VDDCORE_54") (pintype "power_in"))
      (node (ref "U1") (pin "8") (pinfunction "VDDOUT_8") (pintype "power_in"))
    )
    (net (code "74") (name "Net-(U1B-VDDPLL)") (class "Default")
      (node (ref "C10") (pin "2") (pinfunction "2_2") (pintype "passive"))
      (node (ref "C11") (pin "2") (pinfunction "2_2") (pintype "passive"))
      (node (ref "L1") (pin "1") (pinfunction "1_1") (pintype "passive"))
      (node (ref "U1") (pin "64") (pinfunction "VDDPLL_64") (pintype "power_in"))
    )
    (net (code "75") (name "Net-(U2-OUT)") (class "Default")
      (node (ref "C2") (pin "2") (pinfunction "2_2") (pintype "passive"))
      (node (ref "R6") (pin "1") (pinfunction "1_1") (pintype "passive"))
      (node (ref "U2") (pin "5") (pinfunction "OUT_5") (pintype "power_in"))
    )
    (net (code "76") (name "VBUS") (class "Default")
      (node (ref "C16") (pin "2") (pinfunction "2_2") (pintype "passive"))
      (node (ref "H1") (pin "1") (pinfunction "VBUS_1") (pintype "power_in"))
      (node (ref "R3") (pin "2") (pinfunction "2_2") (pintype "passive"))
      (node (ref "TP7") (pin "1") (pinfunction "1_1") (pintype "passive"))
    )
    (net (code "77") (name "unconnected-(H1-ID-Pad4)") (class "Default")
      (node (ref "H1") (pin "4") (pinfunction "ID_4") (pintype "power_in+no_connect"))
    )
    (net (code "78") (name "unconnected-(H2-Pad3)") (class "Default")
      (node (ref "H2") (pin "3") (pinfunction "3_3") (pintype "passive+no_connect"))
    )
    (net (code "79") (name "unconnected-(H2-Pad9)") (class "Default")
      (node (ref "H2") (pin "9") (pinfunction "9_9") (pintype "passive+no_connect"))
    )
    (net (code "80") (name "unconnected-(H2-Pad10)") (class "Default")
      (node (ref "H2") (pin "10") (pinfunction "10_10") (pintype "passive+no_connect"))
    )
    (net (code "81") (name "unconnected-(U1A-JTAGSEL-Pad50)") (class "Default")
      (node (ref "U1") (pin "50") (pinfunction "JTAGSEL_50") (pintype "input+no_connect"))
    )
    (net (code "82") (name "unconnected-(U1A-TST-Pad40)") (class "Default")
      (node (ref "U1") (pin "40") (pinfunction "TST_40") (pintype "input+no_connect"))
    )
    (net (code "83") (name "unconnected-(U2-BYP-Pad4)") (class "Default")
      (node (ref "U2") (pin "4") (pinfunction "BYP_4") (pintype "passive+no_connect"))
    )
  )
)
